# module_tester-v01.net
KiCad netlist of a schematic drawn in EAGLE
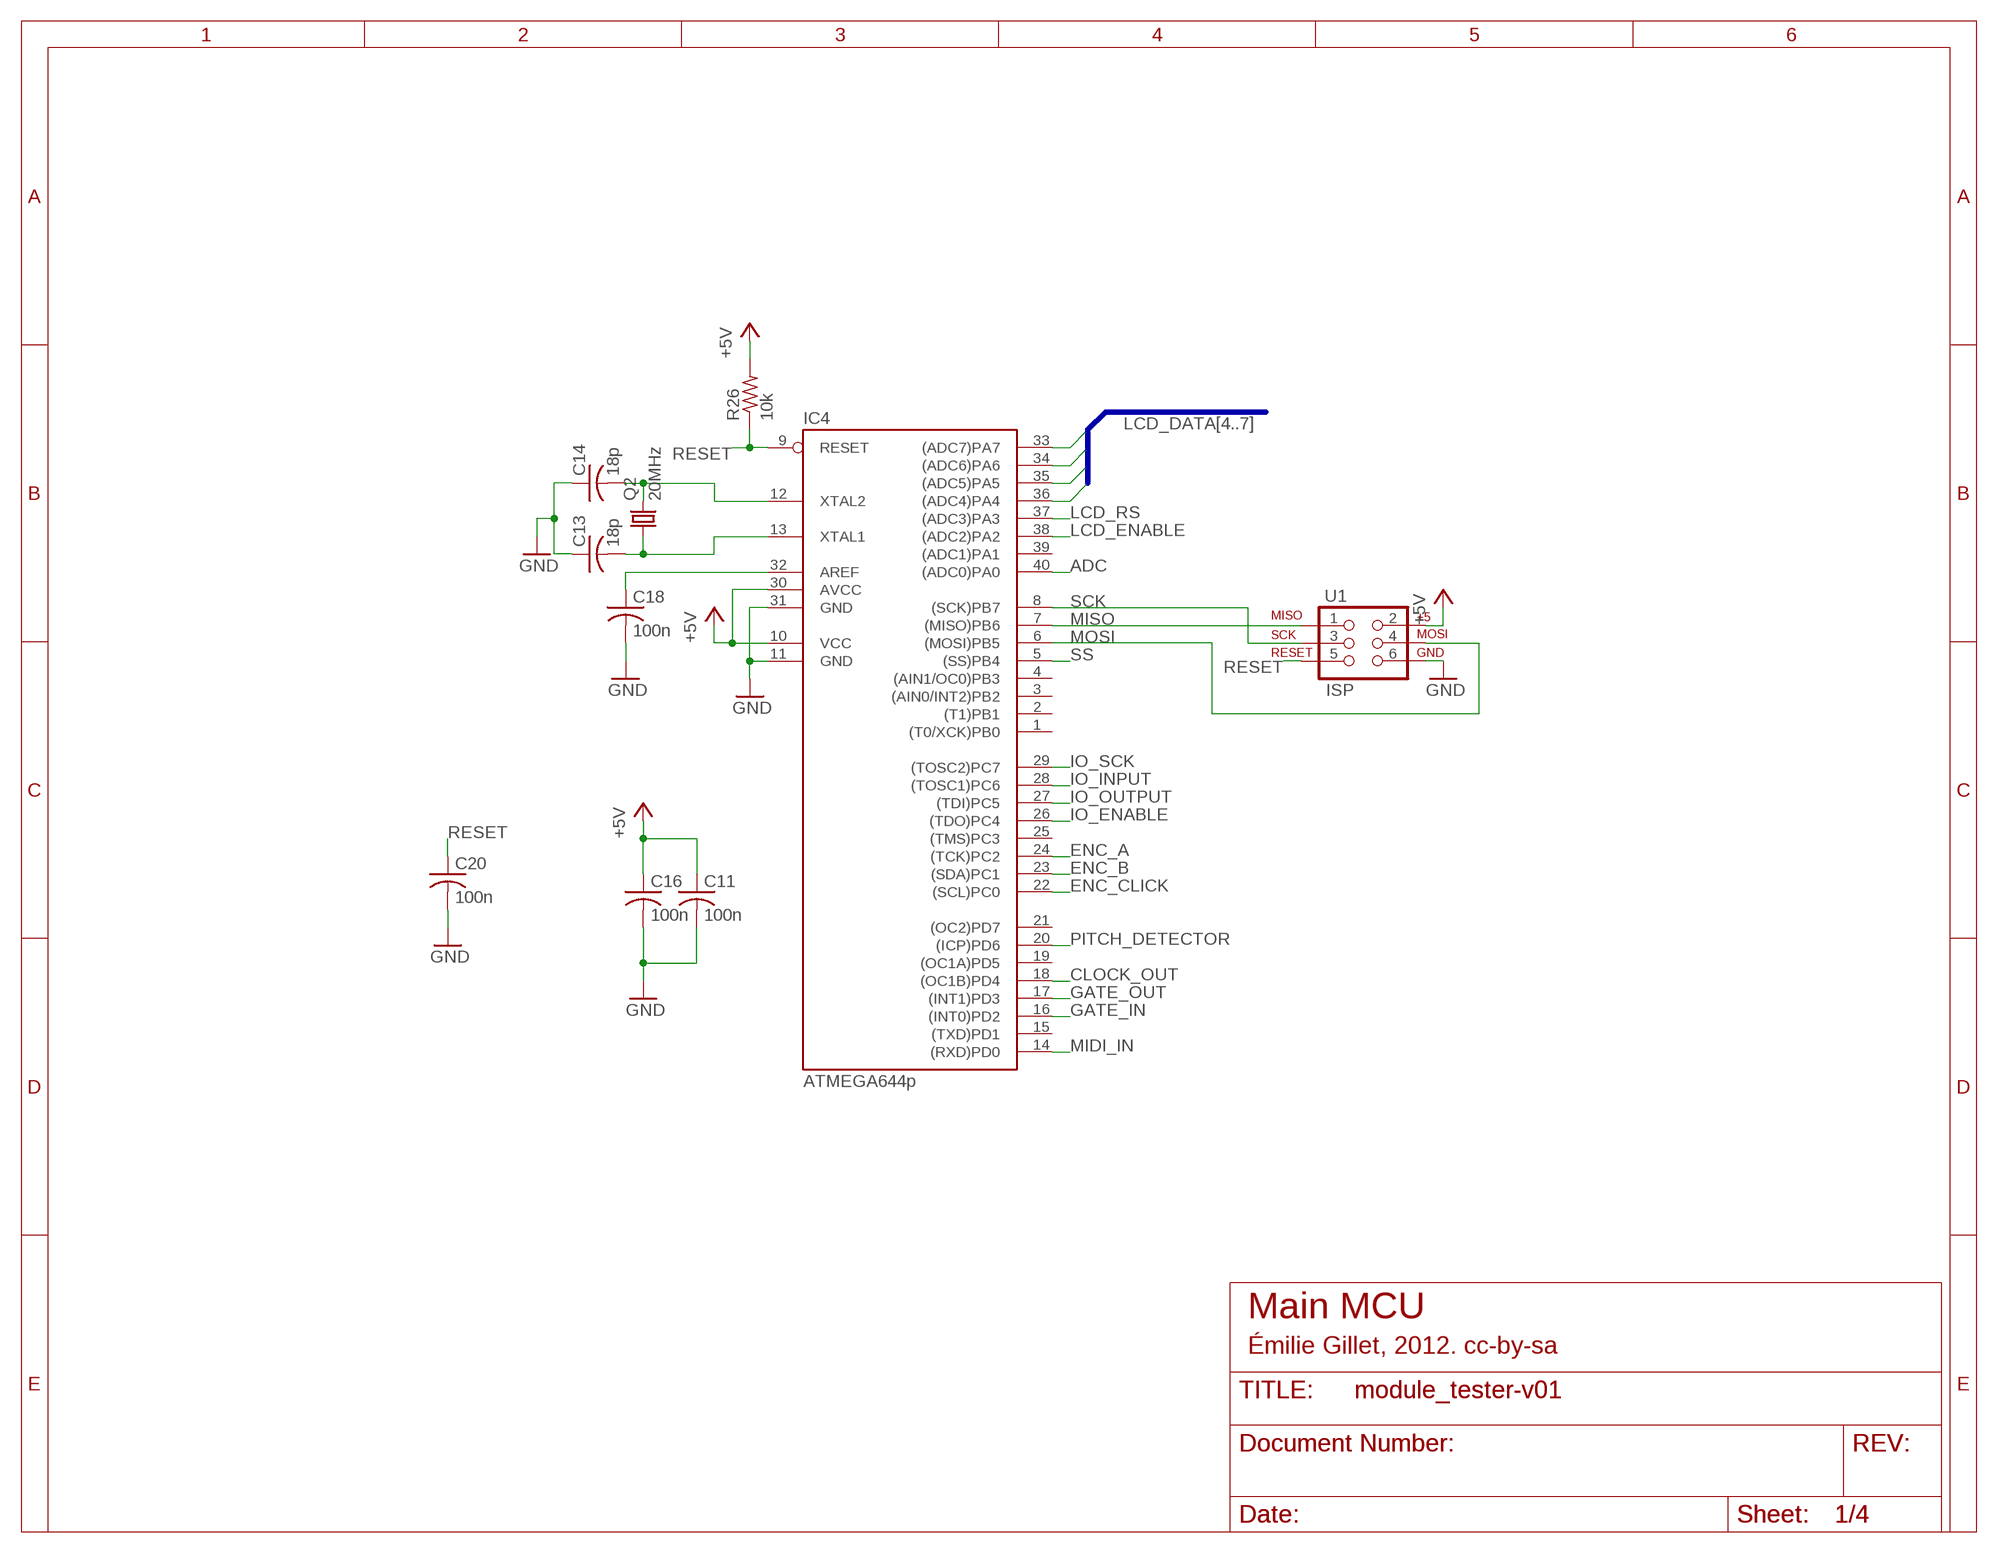
[diagram p0: schematic, sheet 1]
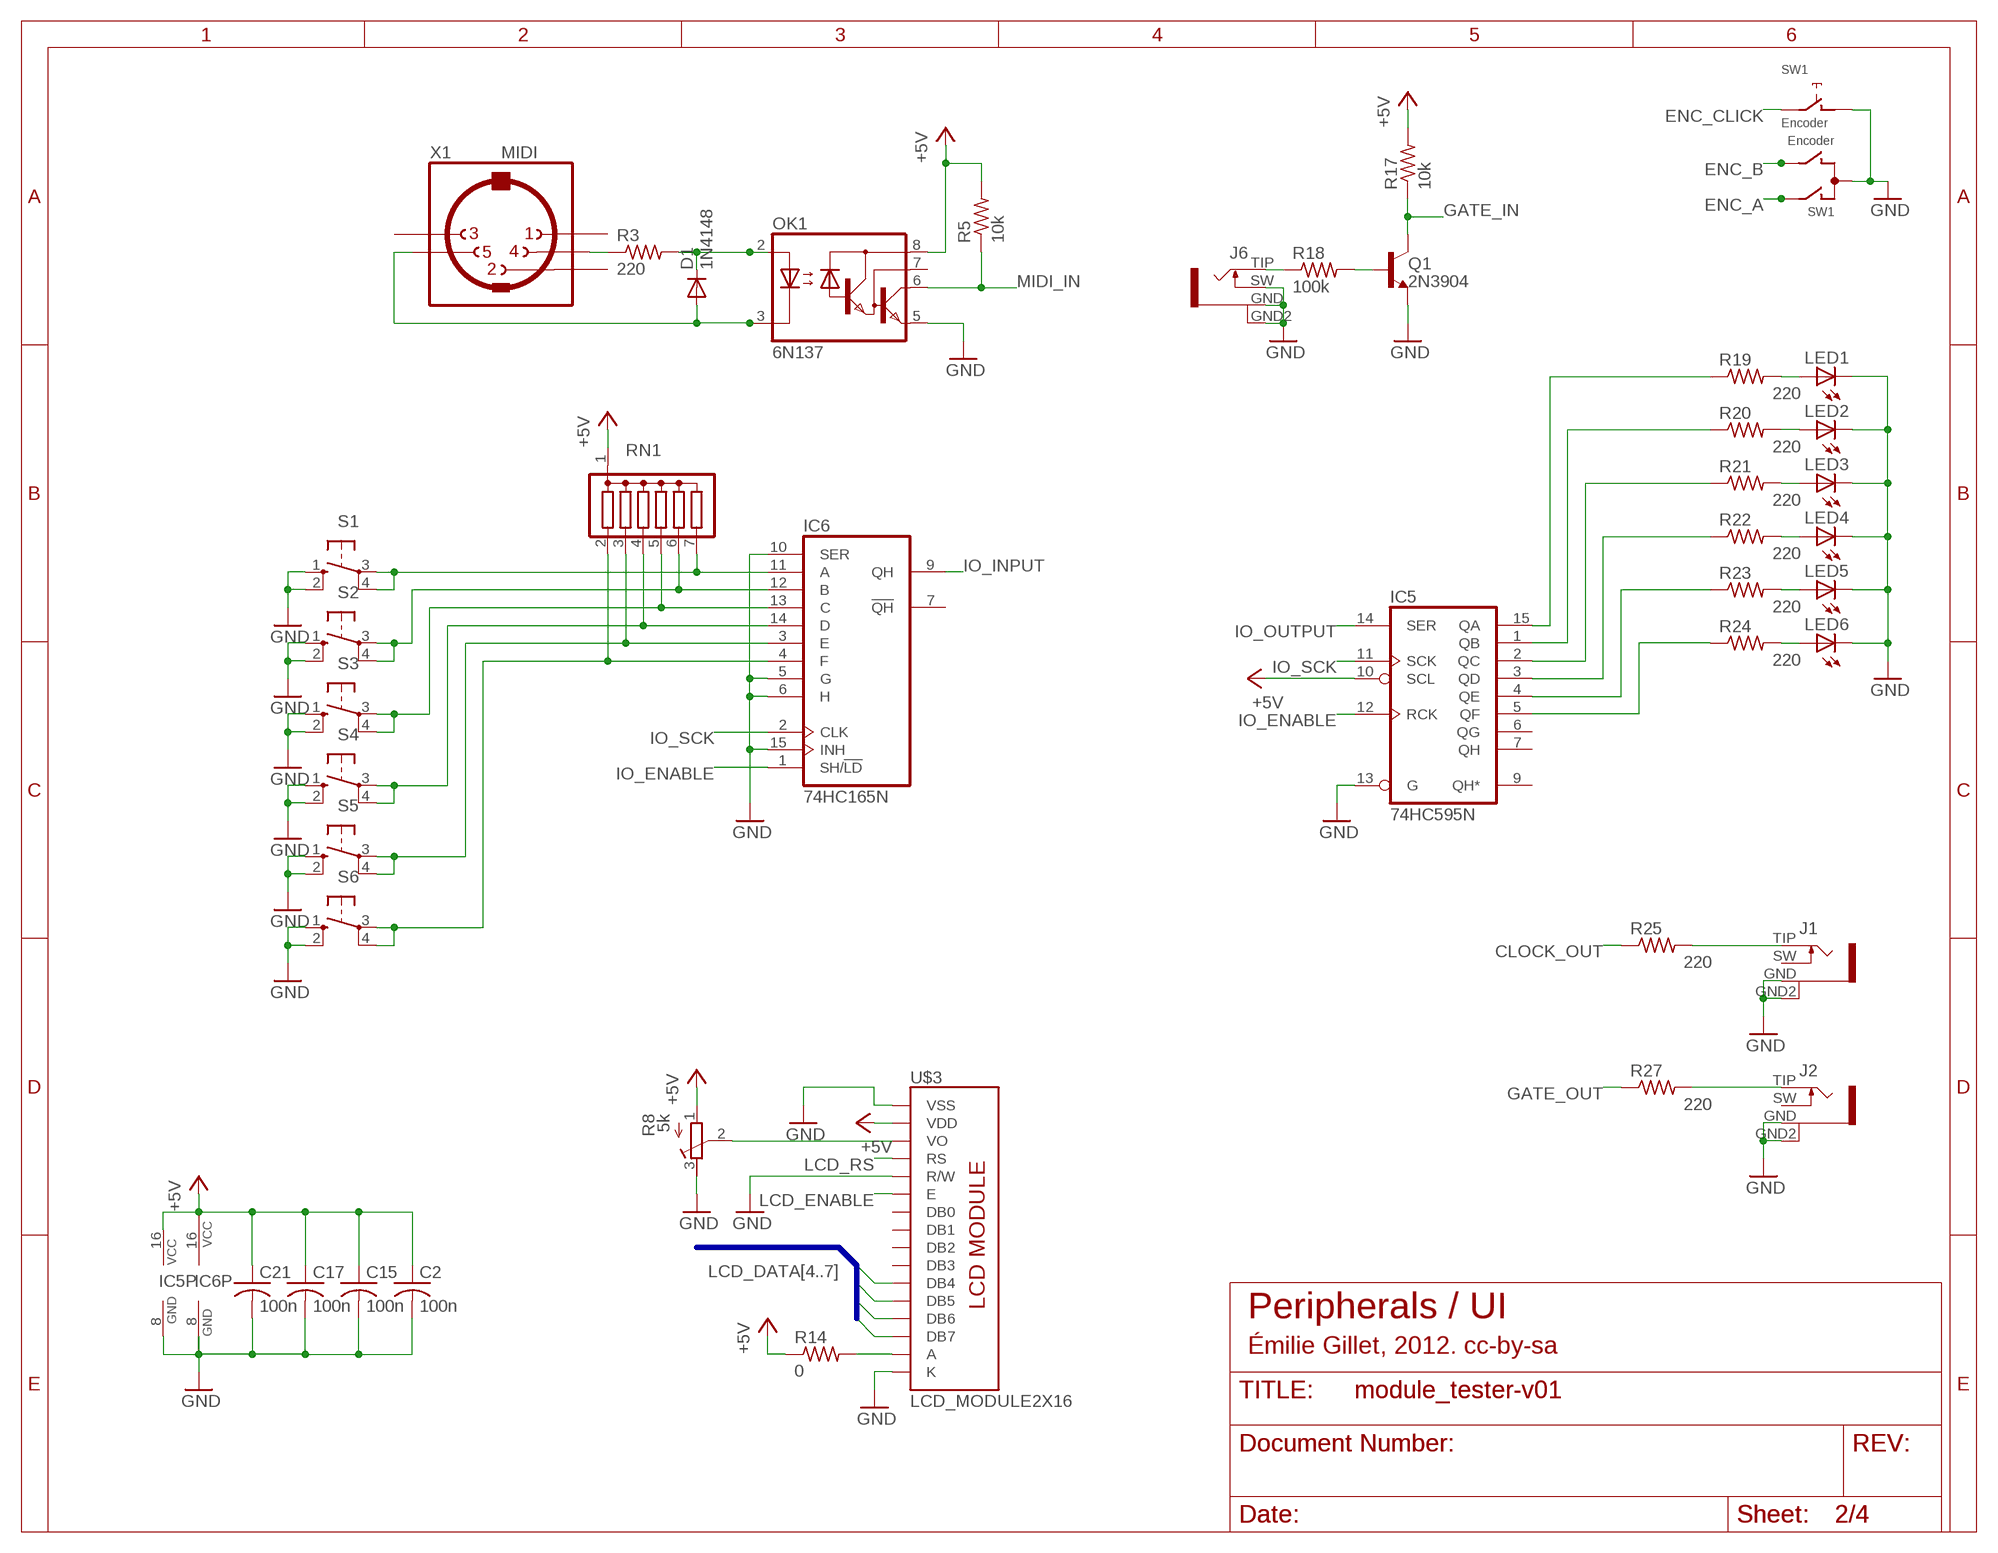
[diagram p1: schematic, sheet 2]
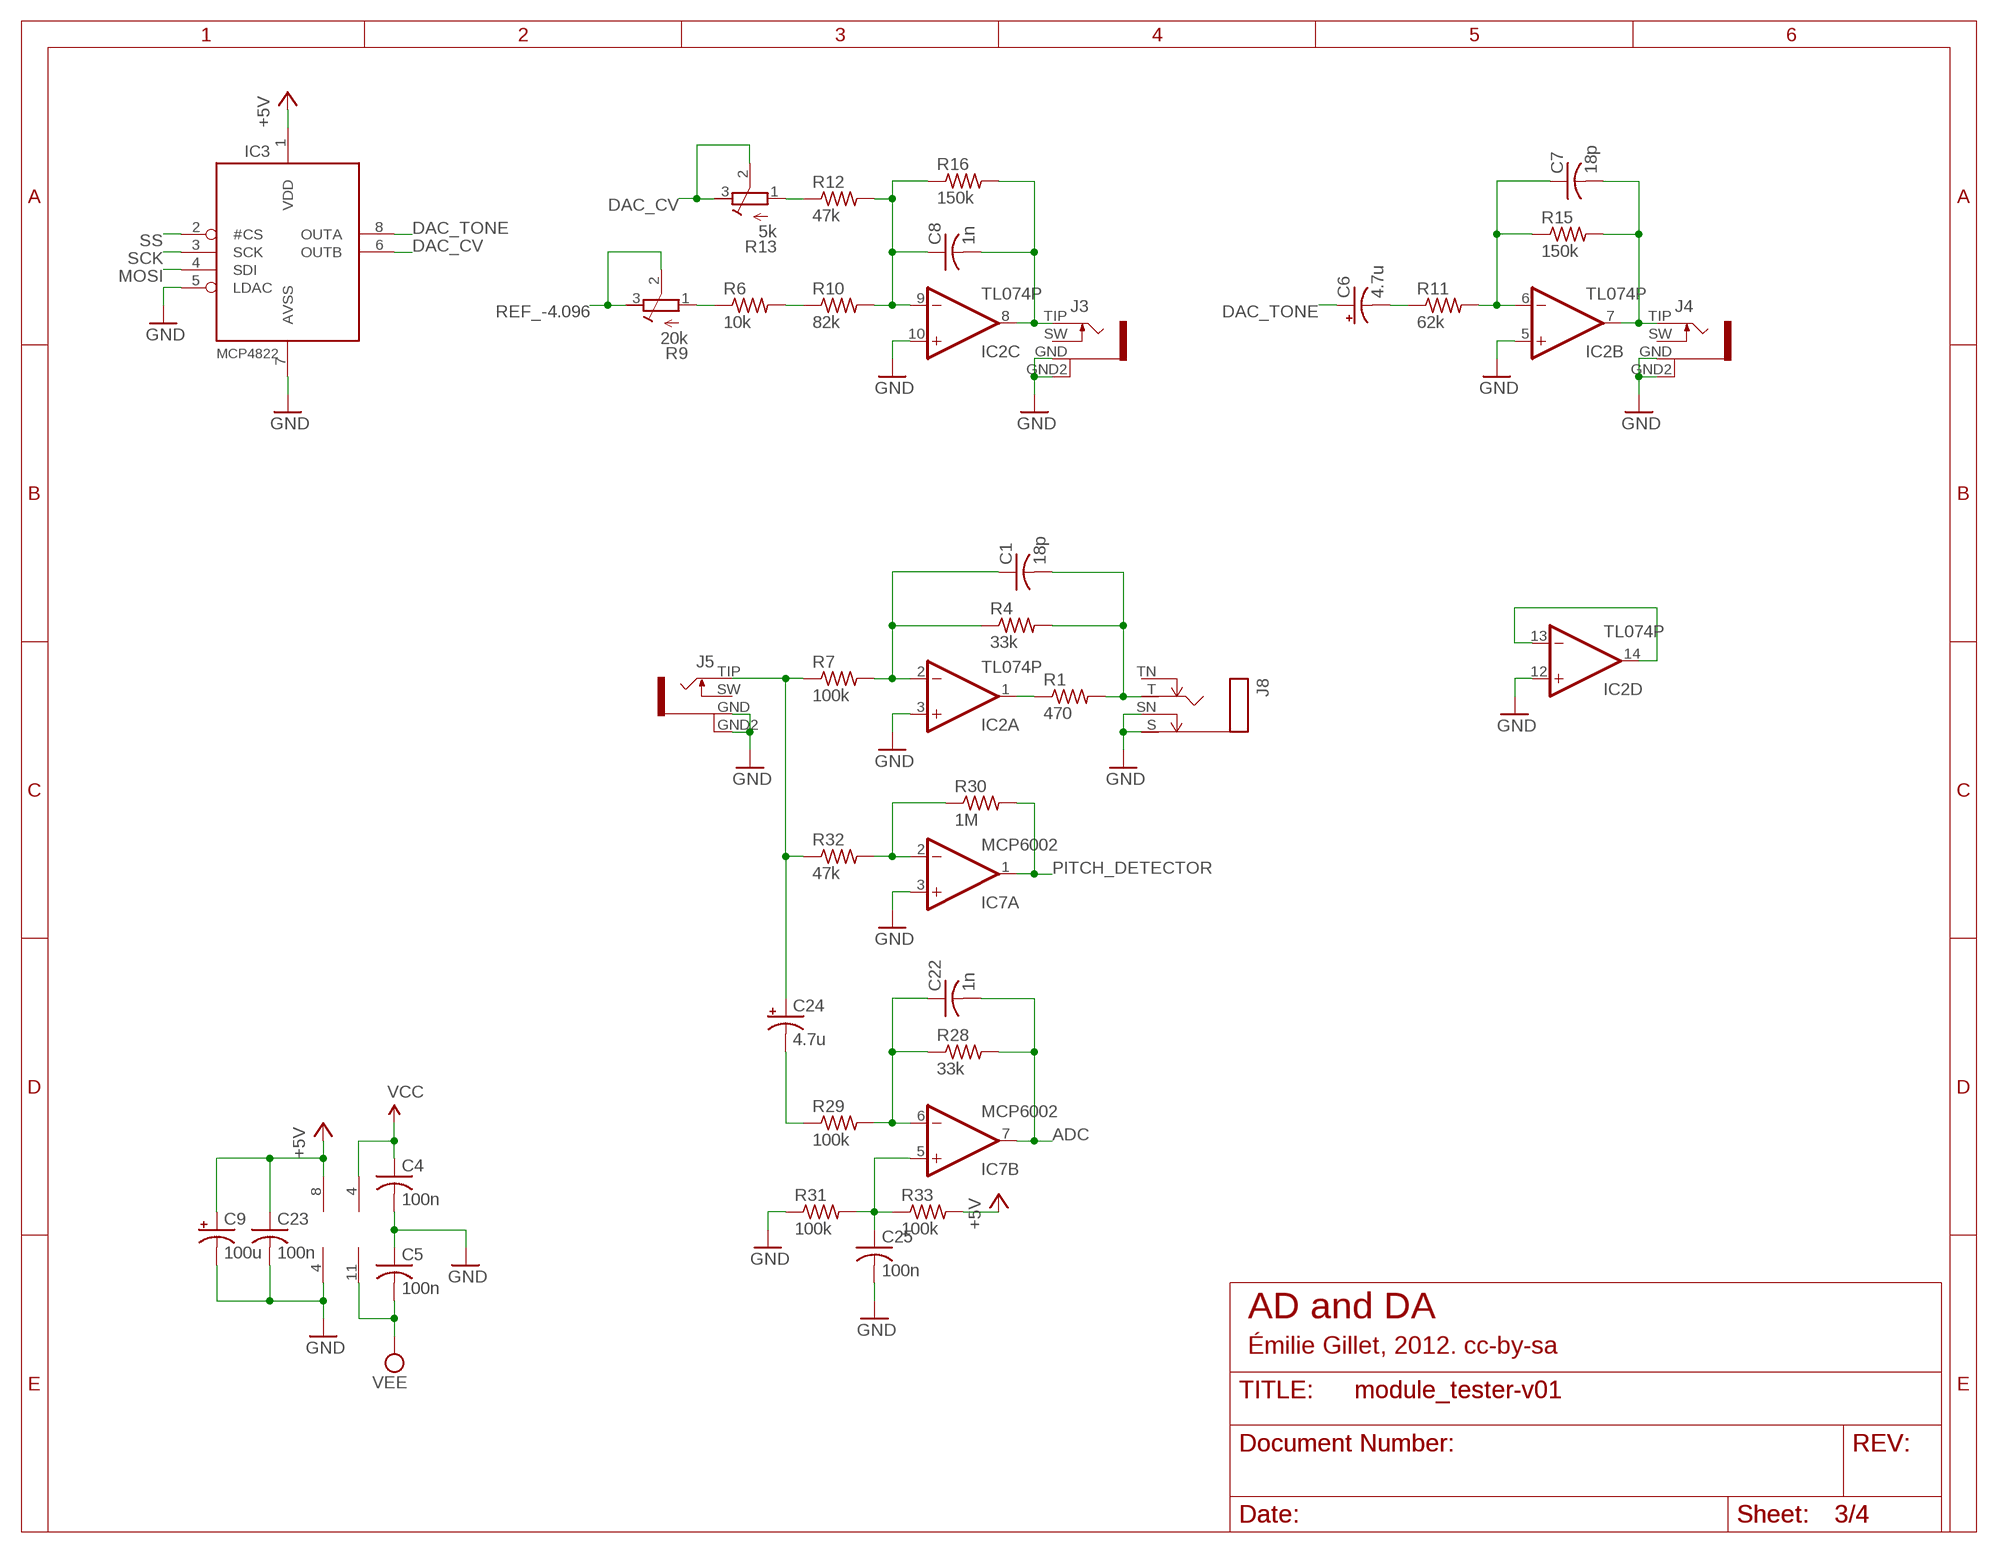
[diagram p2: schematic, sheet 3]
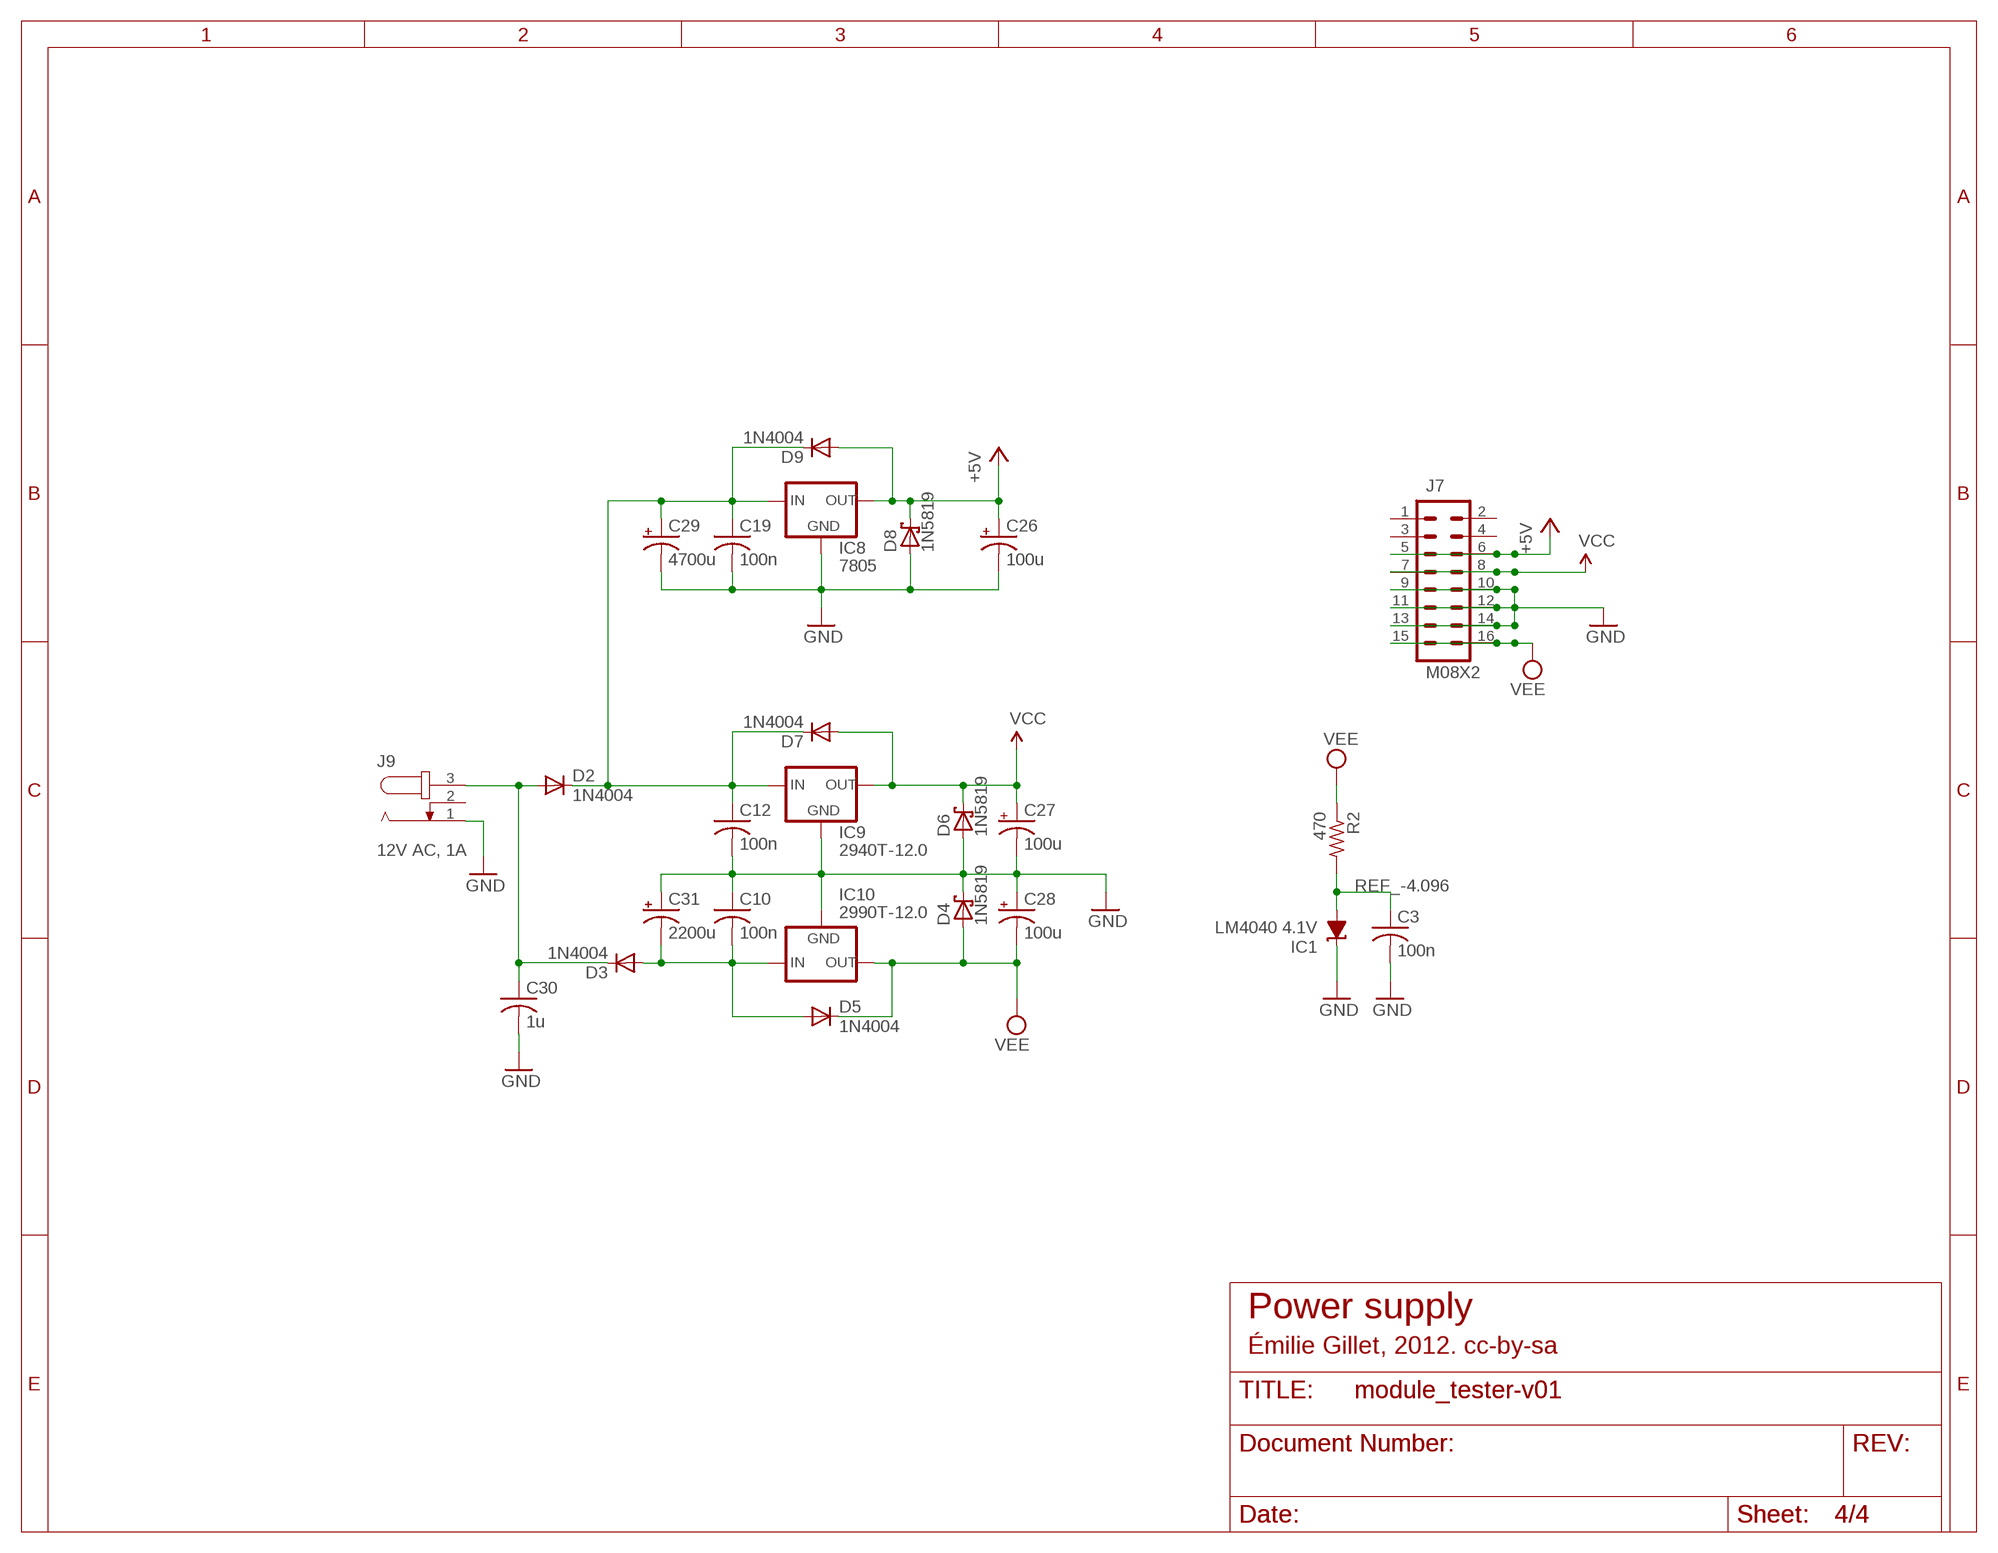
[diagram p3: schematic, sheet 4]

(export (version "E")
  (design (tool "Eeschema 10.0.6"))
  (components
    (comp (ref "C11")
      (value "100n")
      (footprint "eagle-import:C025-025X050")
      (libsource (lib "eagle-import") (part "C-US025-025X050"))
    )
    (comp (ref "C13")
      (value "18p")
      (footprint "eagle-import:C025-025X050")
      (libsource (lib "eagle-import") (part "C-US025-025X050"))
    )
    (comp (ref "C14")
      (value "18p")
      (footprint "eagle-import:C025-025X050")
      (libsource (lib "eagle-import") (part "C-US025-025X050"))
    )
    (comp (ref "C16")
      (value "100n")
      (footprint "eagle-import:C025-025X050")
      (libsource (lib "eagle-import") (part "C-US025-025X050"))
    )
    (comp (ref "C18")
      (value "100n")
      (footprint "eagle-import:C025-025X050")
      (libsource (lib "eagle-import") (part "C-US025-025X050"))
    )
    (comp (ref "C20")
      (value "100n")
      (footprint "eagle-import:C025-025X050")
      (libsource (lib "eagle-import") (part "C-US025-025X050"))
    )
    (comp (ref "IC4")
      (value "ATMEGA644p")
      (footprint "eagle-import:DIL40")
      (libsource (lib "eagle-import") (part "MEGA16-P"))
    )
    (comp (ref "Q2")
      (value "20MHz")
      (footprint "eagle-import:HC49U-V")
      (libsource (lib "eagle-import") (part "CRYSTALHC49U-V"))
    )
    (comp (ref "R26")
      (value "10k")
      (footprint "eagle-import:0204_7")
      (libsource (lib "eagle-import") (part "R-US_0204/7"))
    )
    (comp (ref "U1")
      (value "ISP")
      (footprint "eagle-import:2X3")
      (libsource (lib "eagle-import") (part "AVR_SPI_PRG_6PTH"))
    )
    (comp (ref "C3")
      (value "100n")
      (footprint "eagle-import:C025-025X050")
      (libsource (lib "eagle-import") (part "C-US025-025X050"))
    )
    (comp (ref "C10")
      (value "100n")
      (footprint "eagle-import:C025-025X050")
      (libsource (lib "eagle-import") (part "C-US025-025X050"))
    )
    (comp (ref "C12")
      (value "100n")
      (footprint "eagle-import:C025-025X050")
      (libsource (lib "eagle-import") (part "C-US025-025X050"))
    )
    (comp (ref "C19")
      (value "100n")
      (footprint "eagle-import:C025-025X050")
      (libsource (lib "eagle-import") (part "C-US025-025X050"))
    )
    (comp (ref "C26")
      (value "100u")
      (footprint "eagle-import:E2,5-7")
      (libsource (lib "eagle-import") (part "CPOL-USE2.5-7"))
    )
    (comp (ref "C27")
      (value "100u")
      (footprint "eagle-import:E2,5-7")
      (libsource (lib "eagle-import") (part "CPOL-USE2.5-7"))
    )
    (comp (ref "C28")
      (value "100u")
      (footprint "eagle-import:E2,5-7")
      (libsource (lib "eagle-import") (part "CPOL-USE2.5-7"))
    )
    (comp (ref "C29")
      (value "4700u")
      (footprint "eagle-import:E7,5-16")
      (libsource (lib "eagle-import") (part "CPOL-USE7.5-16"))
    )
    (comp (ref "C30")
      (value "1u")
      (footprint "eagle-import:C075-052X106")
      (libsource (lib "eagle-import") (part "C-US075-052X106"))
    )
    (comp (ref "C31")
      (value "2200u")
      (footprint "eagle-import:E5-13")
      (libsource (lib "eagle-import") (part "CPOL-USE5-13"))
    )
    (comp (ref "D2")
      (value "1N4004")
      (footprint "eagle-import:DO41-10")
      (libsource (lib "eagle-import") (part "1N4004"))
    )
    (comp (ref "D3")
      (value "1N4004")
      (footprint "eagle-import:DO41-10")
      (libsource (lib "eagle-import") (part "1N4004"))
    )
    (comp (ref "D4")
      (value "1N5819")
      (footprint "eagle-import:DO41-7.6")
      (libsource (lib "eagle-import") (part "1N5819-T"))
    )
    (comp (ref "D5")
      (value "1N4004")
      (footprint "eagle-import:DO41-10")
      (libsource (lib "eagle-import") (part "1N4004"))
    )
    (comp (ref "D6")
      (value "1N5819")
      (footprint "eagle-import:DO41-7.6")
      (libsource (lib "eagle-import") (part "1N5819-T"))
    )
    (comp (ref "D7")
      (value "1N4004")
      (footprint "eagle-import:DO41-10")
      (libsource (lib "eagle-import") (part "1N4004"))
    )
    (comp (ref "D8")
      (value "1N5819")
      (footprint "eagle-import:DO41-7.6")
      (libsource (lib "eagle-import") (part "1N5819-T"))
    )
    (comp (ref "D9")
      (value "1N4004")
      (footprint "eagle-import:DO41-10")
      (libsource (lib "eagle-import") (part "1N4004"))
    )
    (comp (ref "IC1")
      (value "LM4040 4.1V")
      (footprint "eagle-import:LP_O-PBCY-W3")
      (libsource (lib "eagle-import") (part "LM4041LPC12"))
    )
    (comp (ref "IC8")
      (value "7805")
      (footprint "eagle-import:78XXS")
      (libsource (lib "eagle-import") (part "78XXS"))
    )
    (comp (ref "IC9")
      (value "2940T-12.0")
      (footprint "eagle-import:78XXL")
      (libsource (lib "eagle-import") (part "78XXL"))
    )
    (comp (ref "IC10")
      (value "2990T-12.0")
      (footprint "eagle-import:79XXS")
      (libsource (lib "eagle-import") (part "79XXS"))
    )
    (comp (ref "J7")
      (value "M08X2")
      (footprint "eagle-import:2X8")
      (libsource (lib "eagle-import") (part "M08X2"))
    )
    (comp (ref "J9")
      (value "JACK-PLUG2")
      (footprint "eagle-import:SPC4078_BIG_HOLES")
      (libsource (lib "eagle-import") (part "JACK-PLUG2"))
    )
    (comp (ref "R2")
      (value "470")
      (footprint "eagle-import:0204_7")
      (libsource (lib "eagle-import") (part "resistor_R-US_0204/7"))
    )
    (comp (ref "C2")
      (value "100n")
      (footprint "eagle-import:C025-025X050")
      (libsource (lib "eagle-import") (part "C-US025-025X050"))
    )
    (comp (ref "C15")
      (value "100n")
      (footprint "eagle-import:C025-025X050")
      (libsource (lib "eagle-import") (part "C-US025-025X050"))
    )
    (comp (ref "C17")
      (value "100n")
      (footprint "eagle-import:C025-025X050")
      (libsource (lib "eagle-import") (part "C-US025-025X050"))
    )
    (comp (ref "C21")
      (value "100n")
      (footprint "eagle-import:C025-025X050")
      (libsource (lib "eagle-import") (part "C-US025-025X050"))
    )
    (comp (ref "D1")
      (value "1N4148")
      (footprint "eagle-import:D-5")
      (libsource (lib "eagle-import") (part "DIODE-D-5"))
    )
    (comp (ref "IC5")
      (value "74HC595N")
      (footprint "eagle-import:DIL16")
      (libsource (lib "eagle-import") (part "74595NHC"))
    )
    (comp (ref "IC6")
      (value "74HC165N")
      (footprint "eagle-import:DIL16")
      (libsource (lib "eagle-import") (part "74165NLS"))
    )
    (comp (ref "J1")
      (value "PJ301WQP")
      (footprint "eagle-import:WQP_PJ_301BM")
      (libsource (lib "eagle-import") (part "PJ301WQP"))
    )
    (comp (ref "J2")
      (value "PJ301WQP")
      (footprint "eagle-import:WQP_PJ_301BM")
      (libsource (lib "eagle-import") (part "PJ301WQP"))
    )
    (comp (ref "J6")
      (value "PJ301WQP")
      (footprint "eagle-import:WQP_PJ_301BM")
      (libsource (lib "eagle-import") (part "PJ301WQP"))
    )
    (comp (ref "LED1")
      (value "LED3MM")
      (footprint "eagle-import:LED3MM")
      (libsource (lib "eagle-import") (part "LED3MM"))
    )
    (comp (ref "LED2")
      (value "LED3MM")
      (footprint "eagle-import:LED3MM")
      (libsource (lib "eagle-import") (part "LED3MM"))
    )
    (comp (ref "LED3")
      (value "LED3MM")
      (footprint "eagle-import:LED3MM")
      (libsource (lib "eagle-import") (part "LED3MM"))
    )
    (comp (ref "LED4")
      (value "LED3MM")
      (footprint "eagle-import:LED3MM")
      (libsource (lib "eagle-import") (part "LED3MM"))
    )
    (comp (ref "LED5")
      (value "LED3MM")
      (footprint "eagle-import:LED3MM")
      (libsource (lib "eagle-import") (part "LED3MM"))
    )
    (comp (ref "LED6")
      (value "LED3MM")
      (footprint "eagle-import:LED3MM")
      (libsource (lib "eagle-import") (part "LED3MM"))
    )
    (comp (ref "OK1")
      (value "6N137")
      (footprint "eagle-import:DIL08")
      (libsource (lib "eagle-import") (part "6N138"))
    )
    (comp (ref "Q1")
      (value "2N3904")
      (footprint "eagle-import:TO92-")
      (libsource (lib "eagle-import") (part "2N3904"))
    )
    (comp (ref "R3")
      (value "220")
      (footprint "eagle-import:0204_7")
      (libsource (lib "eagle-import") (part "R-US_0204/7"))
    )
    (comp (ref "R5")
      (value "10k")
      (footprint "eagle-import:0204_7")
      (libsource (lib "eagle-import") (part "R-US_0204/7"))
    )
    (comp (ref "R8")
      (value "5k")
      (footprint "eagle-import:RTRIM3339P")
      (libsource (lib "eagle-import") (part "R-TRIMM3339P"))
    )
    (comp (ref "R14")
      (value "0")
      (footprint "eagle-import:0204_7")
      (libsource (lib "eagle-import") (part "R-US_0204/7"))
    )
    (comp (ref "R17")
      (value "10k")
      (footprint "eagle-import:0204_7")
      (libsource (lib "eagle-import") (part "R-US_0204/7"))
    )
    (comp (ref "R18")
      (value "100k")
      (footprint "eagle-import:0204_7")
      (libsource (lib "eagle-import") (part "R-US_0204/7"))
    )
    (comp (ref "R19")
      (value "220")
      (footprint "eagle-import:0204_7")
      (libsource (lib "eagle-import") (part "R-US_0204/7"))
    )
    (comp (ref "R20")
      (value "220")
      (footprint "eagle-import:0204_7")
      (libsource (lib "eagle-import") (part "R-US_0204/7"))
    )
    (comp (ref "R21")
      (value "220")
      (footprint "eagle-import:0204_7")
      (libsource (lib "eagle-import") (part "R-US_0204/7"))
    )
    (comp (ref "R22")
      (value "220")
      (footprint "eagle-import:0204_7")
      (libsource (lib "eagle-import") (part "R-US_0204/7"))
    )
    (comp (ref "R23")
      (value "220")
      (footprint "eagle-import:0204_7")
      (libsource (lib "eagle-import") (part "R-US_0204/7"))
    )
    (comp (ref "R24")
      (value "220")
      (footprint "eagle-import:0204_7")
      (libsource (lib "eagle-import") (part "R-US_0204/7"))
    )
    (comp (ref "R25")
      (value "220")
      (footprint "eagle-import:0204_7")
      (libsource (lib "eagle-import") (part "R-US_0204/7"))
    )
    (comp (ref "R27")
      (value "220")
      (footprint "eagle-import:0204_7")
      (libsource (lib "eagle-import") (part "R-US_0204/7"))
    )
    (comp (ref "RN1")
      (value "G06R")
      (footprint "eagle-import:SIL7")
      (libsource (lib "eagle-import") (part "G06R"))
    )
    (comp (ref "S1")
      (value "40-XX")
      (footprint "eagle-import:B3F-40XX")
      (libsource (lib "eagle-import") (part "40-XX"))
    )
    (comp (ref "S2")
      (value "40-XX")
      (footprint "eagle-import:B3F-40XX")
      (libsource (lib "eagle-import") (part "40-XX"))
    )
    (comp (ref "S3")
      (value "40-XX")
      (footprint "eagle-import:B3F-40XX")
      (libsource (lib "eagle-import") (part "40-XX"))
    )
    (comp (ref "S4")
      (value "40-XX")
      (footprint "eagle-import:B3F-40XX")
      (libsource (lib "eagle-import") (part "40-XX"))
    )
    (comp (ref "S5")
      (value "40-XX")
      (footprint "eagle-import:B3F-40XX")
      (libsource (lib "eagle-import") (part "40-XX"))
    )
    (comp (ref "S6")
      (value "40-XX")
      (footprint "eagle-import:B3F-40XX")
      (libsource (lib "eagle-import") (part "40-XX"))
    )
    (comp (ref "SW1")
      (value "Encoder")
      (footprint "eagle-import:ALPS_EC12E_SW")
      (libsource (lib "eagle-import") (part "EC12E_SW"))
    )
    (comp (ref "U$3")
      (value "LCD_MODULE2X16")
      (footprint "eagle-import:LCD_MODULE_2X16")
      (libsource (lib "eagle-import") (part "LCD_MODULE2X16"))
    )
    (comp (ref "X1")
      (value "MIDI")
      (footprint "eagle-import:MAB5SH")
      (libsource (lib "eagle-import") (part "MAB5SH"))
    )
    (comp (ref "C1")
      (value "18p")
      (footprint "eagle-import:C025-025X050")
      (libsource (lib "eagle-import") (part "C-US025-025X050"))
    )
    (comp (ref "C4")
      (value "100n")
      (footprint "eagle-import:C025-025X050")
      (libsource (lib "eagle-import") (part "C-US025-025X050"))
    )
    (comp (ref "C5")
      (value "100n")
      (footprint "eagle-import:C025-025X050")
      (libsource (lib "eagle-import") (part "C-US025-025X050"))
    )
    (comp (ref "C6")
      (value "4.7u")
      (footprint "eagle-import:E2,5-6")
      (libsource (lib "eagle-import") (part "CPOL-USE2.5-6"))
    )
    (comp (ref "C7")
      (value "18p")
      (footprint "eagle-import:C025-025X050")
      (libsource (lib "eagle-import") (part "C-US025-025X050"))
    )
    (comp (ref "C8")
      (value "1n")
      (footprint "eagle-import:C025-025X050")
      (libsource (lib "eagle-import") (part "C-US025-025X050"))
    )
    (comp (ref "C9")
      (value "100u")
      (footprint "eagle-import:E2,5-7")
      (libsource (lib "eagle-import") (part "CPOL-USE2.5-7"))
    )
    (comp (ref "C22")
      (value "1n")
      (footprint "eagle-import:C025-025X050")
      (libsource (lib "eagle-import") (part "C-US025-025X050"))
    )
    (comp (ref "C23")
      (value "100n")
      (footprint "eagle-import:C025-025X050")
      (libsource (lib "eagle-import") (part "C-US025-025X050"))
    )
    (comp (ref "C24")
      (value "4.7u")
      (footprint "eagle-import:E2,5-6")
      (libsource (lib "eagle-import") (part "CPOL-USE2.5-6"))
    )
    (comp (ref "C25")
      (value "100n")
      (footprint "eagle-import:C025-025X050")
      (libsource (lib "eagle-import") (part "C-US025-025X050"))
    )
    (comp (ref "IC2")
      (value "TL074P")
      (footprint "eagle-import:DIL14")
      (libsource (lib "eagle-import") (part "TL074P"))
    )
    (comp (ref "IC3")
      (value "MCP4822")
      (footprint "eagle-import:DIL08")
      (libsource (lib "eagle-import") (part "MCP4822"))
    )
    (comp (ref "IC7")
      (value "MCP6002")
      (footprint "eagle-import:DIL08")
      (libsource (lib "eagle-import") (part "TL072P"))
    )
    (comp (ref "J3")
      (value "PJ301WQP")
      (footprint "eagle-import:WQP_PJ_301BM")
      (libsource (lib "eagle-import") (part "PJ301WQP"))
    )
    (comp (ref "J4")
      (value "PJ301WQP")
      (footprint "eagle-import:WQP_PJ_301BM")
      (libsource (lib "eagle-import") (part "PJ301WQP"))
    )
    (comp (ref "J5")
      (value "PJ301WQP")
      (footprint "eagle-import:WQP_PJ_301BM")
      (libsource (lib "eagle-import") (part "PJ301WQP"))
    )
    (comp (ref "J8")
      (value "MONOSWSLIM")
      (footprint "eagle-import:NRJ4HF")
      (libsource (lib "eagle-import") (part "MONOSWSLIM"))
    )
    (comp (ref "R1")
      (value "470")
      (footprint "eagle-import:0204_7")
      (libsource (lib "eagle-import") (part "R-US_0204/7"))
    )
    (comp (ref "R4")
      (value "33k")
      (footprint "eagle-import:0204_7")
      (libsource (lib "eagle-import") (part "R-US_0204/7"))
    )
    (comp (ref "R6")
      (value "10k")
      (footprint "eagle-import:0204_7")
      (libsource (lib "eagle-import") (part "R-US_0204/7"))
    )
    (comp (ref "R7")
      (value "100k")
      (footprint "eagle-import:0204_7")
      (libsource (lib "eagle-import") (part "R-US_0204/7"))
    )
    (comp (ref "R9")
      (value "20k")
      (footprint "eagle-import:RTRIM3296W")
      (libsource (lib "eagle-import") (part "R-TRIMM3296W"))
    )
    (comp (ref "R10")
      (value "82k")
      (footprint "eagle-import:0204_7")
      (libsource (lib "eagle-import") (part "R-US_0204/7"))
    )
    (comp (ref "R11")
      (value "62k")
      (footprint "eagle-import:0204_7")
      (libsource (lib "eagle-import") (part "R-US_0204/7"))
    )
    (comp (ref "R12")
      (value "47k")
      (footprint "eagle-import:0204_7")
      (libsource (lib "eagle-import") (part "R-US_0204/7"))
    )
    (comp (ref "R13")
      (value "5k")
      (footprint "eagle-import:RTRIM3296W")
      (libsource (lib "eagle-import") (part "R-TRIMM3296W"))
    )
    (comp (ref "R15")
      (value "150k")
      (footprint "eagle-import:0204_7")
      (libsource (lib "eagle-import") (part "R-US_0204/7"))
    )
    (comp (ref "R16")
      (value "150k")
      (footprint "eagle-import:0204_7")
      (libsource (lib "eagle-import") (part "R-US_0204/7"))
    )
    (comp (ref "R28")
      (value "33k")
      (footprint "eagle-import:0204_7")
      (libsource (lib "eagle-import") (part "R-US_0204/7"))
    )
    (comp (ref "R29")
      (value "100k")
      (footprint "eagle-import:0204_7")
      (libsource (lib "eagle-import") (part "R-US_0204/7"))
    )
    (comp (ref "R30")
      (value "1M")
      (footprint "eagle-import:0204_7")
      (libsource (lib "eagle-import") (part "R-US_0204/7"))
    )
    (comp (ref "R31")
      (value "100k")
      (footprint "eagle-import:0204_7")
      (libsource (lib "eagle-import") (part "R-US_0204/7"))
    )
    (comp (ref "R32")
      (value "47k")
      (footprint "eagle-import:0204_7")
      (libsource (lib "eagle-import") (part "R-US_0204/7"))
    )
    (comp (ref "R33")
      (value "100k")
      (footprint "eagle-import:0204_7")
      (libsource (lib "eagle-import") (part "R-US_0204/7"))
    )
  )
  (nets
    (net (code "1") (name "+5V") (class "Default")
      (node (ref "C11") (pin "1") (pinfunction "1_1") (pintype "passive"))
      (node (ref "C15") (pin "1") (pinfunction "1_1") (pintype "passive"))
      (node (ref "C16") (pin "1") (pinfunction "1_1") (pintype "passive"))
      (node (ref "C17") (pin "1") (pinfunction "1_1") (pintype "passive"))
      (node (ref "C2") (pin "1") (pinfunction "1_1") (pintype "passive"))
      (node (ref "C21") (pin "1") (pinfunction "1_1") (pintype "passive"))
      (node (ref "C23") (pin "1") (pinfunction "1_1") (pintype "passive"))
      (node (ref "C26") (pin "+") (pinfunction "+_+") (pintype "passive"))
      (node (ref "C9") (pin "+") (pinfunction "+_+") (pintype "passive"))
      (node (ref "D8") (pin "C") (pinfunction "C_C") (pintype "passive"))
      (node (ref "D9") (pin "A") (pinfunction "A_A") (pintype "passive"))
      (node (ref "IC3") (pin "1") (pinfunction "VDD_1") (pintype "power_in"))
      (node (ref "IC4") (pin "10") (pinfunction "VCC_10") (pintype "power_in"))
      (node (ref "IC4") (pin "30") (pinfunction "AVCC_30") (pintype "power_in"))
      (node (ref "IC5") (pin "10") (pinfunction "SCL_10") (pintype "input"))
      (node (ref "IC5") (pin "16") (pinfunction "VCC_16") (pintype "power_in"))
      (node (ref "IC6") (pin "16") (pinfunction "VCC_16") (pintype "power_in"))
      (node (ref "IC7") (pin "8") (pinfunction "V+_8") (pintype "power_in"))
      (node (ref "IC8") (pin "OUT") (pinfunction "OUT_OUT") (pintype "passive"))
      (node (ref "J7") (pin "5") (pinfunction "5_5") (pintype "passive"))
      (node (ref "J7") (pin "6") (pinfunction "6_6") (pintype "passive"))
      (node (ref "OK1") (pin "8") (pinfunction "VCC_8") (pintype "passive"))
      (node (ref "R14") (pin "1") (pinfunction "1_1") (pintype "passive"))
      (node (ref "R17") (pin "2") (pinfunction "2_2") (pintype "passive"))
      (node (ref "R26") (pin "2") (pinfunction "2_2") (pintype "passive"))
      (node (ref "R33") (pin "2") (pinfunction "2_2") (pintype "passive"))
      (node (ref "R5") (pin "2") (pinfunction "2_2") (pintype "passive"))
      (node (ref "R8") (pin "1") (pinfunction "E_1") (pintype "passive"))
      (node (ref "RN1") (pin "1") (pinfunction "1_1") (pintype "passive"))
      (node (ref "U$3") (pin "2") (pinfunction "VDD_2") (pintype "power_in"))
      (node (ref "U1") (pin "2") (pinfunction "2_2") (pintype "passive"))
    )
    (net (code "4") (name "ADC") (class "Default")
      (node (ref "C22") (pin "2") (pinfunction "2_2") (pintype "passive"))
      (node (ref "IC4") (pin "40") (pinfunction "(ADC0)PA0_40") (pintype "bidirectional"))
      (node (ref "IC7") (pin "7") (pinfunction "OUT_7") (pintype "output"))
      (node (ref "R28") (pin "2") (pinfunction "2_2") (pintype "passive"))
    )
    (net (code "5") (name "CLOCK_OUT") (class "Default")
      (node (ref "IC4") (pin "18") (pinfunction "(OC1B)PD4_18") (pintype "bidirectional"))
      (node (ref "R25") (pin "1") (pinfunction "1_1") (pintype "passive"))
    )
    (net (code "6") (name "DAC_CV") (class "Default")
      (node (ref "IC3") (pin "6") (pinfunction "OUTB_6") (pintype "output"))
      (node (ref "R13") (pin "2") (pinfunction "S_2") (pintype "passive"))
      (node (ref "R13") (pin "3") (pinfunction "A_3") (pintype "passive"))
    )
    (net (code "7") (name "DAC_TONE") (class "Default")
      (node (ref "C6") (pin "+") (pinfunction "+_+") (pintype "passive"))
      (node (ref "IC3") (pin "8") (pinfunction "OUTA_8") (pintype "output"))
    )
    (net (code "8") (name "ENC_A") (class "Default")
      (node (ref "IC4") (pin "24") (pinfunction "(TCK)PC2_24") (pintype "bidirectional"))
      (node (ref "SW1") (pin "A") (pinfunction "A_A") (pintype "passive"))
    )
    (net (code "9") (name "ENC_B") (class "Default")
      (node (ref "IC4") (pin "23") (pinfunction "(SDA)PC1_23") (pintype "bidirectional"))
      (node (ref "SW1") (pin "B") (pinfunction "B_B") (pintype "passive"))
    )
    (net (code "10") (name "ENC_CLICK") (class "Default")
      (node (ref "IC4") (pin "22") (pinfunction "(SCL)PC0_22") (pintype "bidirectional"))
      (node (ref "SW1") (pin "E") (pinfunction "2_E") (pintype "passive"))
    )
    (net (code "11") (name "GATE_IN") (class "Default")
      (node (ref "IC4") (pin "16") (pinfunction "(INT0)PD2_16") (pintype "bidirectional"))
      (node (ref "Q1") (pin "1") (pinfunction "C_1") (pintype "passive"))
      (node (ref "R17") (pin "1") (pinfunction "1_1") (pintype "passive"))
    )
    (net (code "12") (name "GATE_OUT") (class "Default")
      (node (ref "IC4") (pin "17") (pinfunction "(INT1)PD3_17") (pintype "bidirectional"))
      (node (ref "R27") (pin "1") (pinfunction "1_1") (pintype "passive"))
    )
    (net (code "13") (name "GND") (class "Default")
      (node (ref "C10") (pin "1") (pinfunction "1_1") (pintype "passive"))
      (node (ref "C11") (pin "2") (pinfunction "2_2") (pintype "passive"))
      (node (ref "C12") (pin "2") (pinfunction "2_2") (pintype "passive"))
      (node (ref "C13") (pin "1") (pinfunction "1_1") (pintype "passive"))
      (node (ref "C14") (pin "1") (pinfunction "1_1") (pintype "passive"))
      (node (ref "C15") (pin "2") (pinfunction "2_2") (pintype "passive"))
      (node (ref "C16") (pin "2") (pinfunction "2_2") (pintype "passive"))
      (node (ref "C17") (pin "2") (pinfunction "2_2") (pintype "passive"))
      (node (ref "C18") (pin "2") (pinfunction "2_2") (pintype "passive"))
      (node (ref "C19") (pin "2") (pinfunction "2_2") (pintype "passive"))
      (node (ref "C2") (pin "2") (pinfunction "2_2") (pintype "passive"))
      (node (ref "C20") (pin "2") (pinfunction "2_2") (pintype "passive"))
      (node (ref "C21") (pin "2") (pinfunction "2_2") (pintype "passive"))
      (node (ref "C23") (pin "2") (pinfunction "2_2") (pintype "passive"))
      (node (ref "C25") (pin "2") (pinfunction "2_2") (pintype "passive"))
      (node (ref "C26") (pin "-") (pinfunction "-_-") (pintype "passive"))
      (node (ref "C27") (pin "-") (pinfunction "-_-") (pintype "passive"))
      (node (ref "C28") (pin "+") (pinfunction "+_+") (pintype "passive"))
      (node (ref "C29") (pin "-") (pinfunction "-_-") (pintype "passive"))
      (node (ref "C3") (pin "2") (pinfunction "2_2") (pintype "passive"))
      (node (ref "C30") (pin "2") (pinfunction "2_2") (pintype "passive"))
      (node (ref "C31") (pin "+") (pinfunction "+_+") (pintype "passive"))
      (node (ref "C4") (pin "2") (pinfunction "2_2") (pintype "passive"))
      (node (ref "C5") (pin "1") (pinfunction "1_1") (pintype "passive"))
      (node (ref "C9") (pin "-") (pinfunction "-_-") (pintype "passive"))
      (node (ref "D4") (pin "C") (pinfunction "C_C") (pintype "passive"))
      (node (ref "D6") (pin "A") (pinfunction "A_A") (pintype "passive"))
      (node (ref "D8") (pin "A") (pinfunction "A_A") (pintype "passive"))
      (node (ref "IC1") (pin "2") (pinfunction "C_2") (pintype "passive"))
      (node (ref "IC10") (pin "GND") (pinfunction "GND_GND") (pintype "input"))
      (node (ref "IC2") (pin "10") (pinfunction "+IN_10") (pintype "input"))
      (node (ref "IC2") (pin "12") (pinfunction "+IN_12") (pintype "input"))
      (node (ref "IC2") (pin "3") (pinfunction "+IN_3") (pintype "input"))
      (node (ref "IC2") (pin "5") (pinfunction "+IN_5") (pintype "input"))
      (node (ref "IC3") (pin "5") (pinfunction "LDAC_5") (pintype "input"))
      (node (ref "IC3") (pin "7") (pinfunction "AVSS_7") (pintype "power_in"))
      (node (ref "IC4") (pin "11") (pinfunction "GND_11") (pintype "power_in"))
      (node (ref "IC4") (pin "31") (pinfunction "GND_31") (pintype "power_in"))
      (node (ref "IC5") (pin "13") (pinfunction "G_13") (pintype "input"))
      (node (ref "IC5") (pin "8") (pinfunction "GND_8") (pintype "power_in"))
      (node (ref "IC6") (pin "10") (pinfunction "SER_10") (pintype "input"))
      (node (ref "IC6") (pin "15") (pinfunction "INH_15") (pintype "input"))
      (node (ref "IC6") (pin "5") (pinfunction "G_5") (pintype "input"))
      (node (ref "IC6") (pin "6") (pinfunction "H_6") (pintype "input"))
      (node (ref "IC6") (pin "8") (pinfunction "GND_8") (pintype "power_in"))
      (node (ref "IC7") (pin "3") (pinfunction "+IN_3") (pintype "input"))
      (node (ref "IC7") (pin "4") (pinfunction "V-_4") (pintype "power_in"))
      (node (ref "IC8") (pin "GND") (pinfunction "GND_GND") (pintype "input"))
      (node (ref "IC9") (pin "GND") (pinfunction "GND_GND") (pintype "input"))
      (node (ref "J1") (pin "GND") (pinfunction "1_GND") (pintype "passive"))
      (node (ref "J1") (pin "GND2") (pinfunction "4_GND2") (pintype "passive"))
      (node (ref "J2") (pin "GND") (pinfunction "1_GND") (pintype "passive"))
      (node (ref "J2") (pin "GND2") (pinfunction "4_GND2") (pintype "passive"))
      (node (ref "J3") (pin "GND") (pinfunction "1_GND") (pintype "passive"))
      (node (ref "J3") (pin "GND2") (pinfunction "4_GND2") (pintype "passive"))
      (node (ref "J4") (pin "GND") (pinfunction "1_GND") (pintype "passive"))
      (node (ref "J4") (pin "GND2") (pinfunction "4_GND2") (pintype "passive"))
      (node (ref "J5") (pin "GND") (pinfunction "1_GND") (pintype "passive"))
      (node (ref "J5") (pin "GND2") (pinfunction "4_GND2") (pintype "passive"))
      (node (ref "J6") (pin "GND") (pinfunction "1_GND") (pintype "passive"))
      (node (ref "J6") (pin "GND2") (pinfunction "4_GND2") (pintype "passive"))
      (node (ref "J6") (pin "SW") (pinfunction "3_SW") (pintype "passive"))
      (node (ref "J7") (pin "10") (pinfunction "10_10") (pintype "passive"))
      (node (ref "J7") (pin "11") (pinfunction "11_11") (pintype "passive"))
      (node (ref "J7") (pin "12") (pinfunction "12_12") (pintype "passive"))
      (node (ref "J7") (pin "13") (pinfunction "13_13") (pintype "passive"))
      (node (ref "J7") (pin "14") (pinfunction "14_14") (pintype "passive"))
      (node (ref "J7") (pin "9") (pinfunction "9_9") (pintype "passive"))
      (node (ref "J8") (pin "S") (pinfunction "S_S") (pintype "passive"))
      (node (ref "J8") (pin "SN") (pinfunction "SN_SN") (pintype "passive"))
      (node (ref "J9") (pin "1") (pinfunction "1_1") (pintype "passive"))
      (node (ref "LED1") (pin "K") (pinfunction "C_K") (pintype "passive"))
      (node (ref "LED2") (pin "K") (pinfunction "C_K") (pintype "passive"))
      (node (ref "LED3") (pin "K") (pinfunction "C_K") (pintype "passive"))
      (node (ref "LED4") (pin "K") (pinfunction "C_K") (pintype "passive"))
      (node (ref "LED5") (pin "K") (pinfunction "C_K") (pintype "passive"))
      (node (ref "LED6") (pin "K") (pinfunction "C_K") (pintype "passive"))
      (node (ref "OK1") (pin "5") (pinfunction "GND_5") (pintype "passive"))
      (node (ref "Q1") (pin "3") (pinfunction "E_3") (pintype "passive"))
      (node (ref "R31") (pin "1") (pinfunction "1_1") (pintype "passive"))
      (node (ref "R8") (pin "3") (pinfunction "A_3") (pintype "passive"))
      (node (ref "S1") (pin "1") (pinfunction "S_1") (pintype "passive"))
      (node (ref "S1") (pin "2") (pinfunction "S1_2") (pintype "passive"))
      (node (ref "S2") (pin "1") (pinfunction "S_1") (pintype "passive"))
      (node (ref "S2") (pin "2") (pinfunction "S1_2") (pintype "passive"))
      (node (ref "S3") (pin "1") (pinfunction "S_1") (pintype "passive"))
      (node (ref "S3") (pin "2") (pinfunction "S1_2") (pintype "passive"))
      (node (ref "S4") (pin "1") (pinfunction "S_1") (pintype "passive"))
      (node (ref "S4") (pin "2") (pinfunction "S1_2") (pintype "passive"))
      (node (ref "S5") (pin "1") (pinfunction "S_1") (pintype "passive"))
      (node (ref "S5") (pin "2") (pinfunction "S1_2") (pintype "passive"))
      (node (ref "S6") (pin "1") (pinfunction "S_1") (pintype "passive"))
      (node (ref "S6") (pin "2") (pinfunction "S1_2") (pintype "passive"))
      (node (ref "SW1") (pin "C") (pinfunction "C_C") (pintype "passive"))
      (node (ref "SW1") (pin "D") (pinfunction "1_D") (pintype "passive"))
      (node (ref "U$3") (pin "1") (pinfunction "VSS_1") (pintype "power_in"))
      (node (ref "U$3") (pin "16") (pinfunction "K_16") (pintype "power_in"))
      (node (ref "U$3") (pin "5") (pinfunction "R/W_5") (pintype "input"))
      (node (ref "U1") (pin "6") (pinfunction "6_6") (pintype "passive"))
    )
    (net (code "14") (name "IO_ENABLE") (class "Default")
      (node (ref "IC4") (pin "26") (pinfunction "(TDO)PC4_26") (pintype "bidirectional"))
      (node (ref "IC5") (pin "12") (pinfunction "RCK_12") (pintype "input"))
      (node (ref "IC6") (pin "1") (pinfunction "SH/~{LD}_1") (pintype "input"))
    )
    (net (code "15") (name "IO_INPUT") (class "Default")
      (node (ref "IC4") (pin "28") (pinfunction "(TOSC1)PC6_28") (pintype "bidirectional"))
      (node (ref "IC6") (pin "9") (pinfunction "QH_9") (pintype "output"))
    )
    (net (code "16") (name "IO_OUTPUT") (class "Default")
      (node (ref "IC4") (pin "27") (pinfunction "(TDI)PC5_27") (pintype "bidirectional"))
      (node (ref "IC5") (pin "14") (pinfunction "SER_14") (pintype "input"))
    )
    (net (code "17") (name "IO_SCK") (class "Default")
      (node (ref "IC4") (pin "29") (pinfunction "(TOSC2)PC7_29") (pintype "bidirectional"))
      (node (ref "IC5") (pin "11") (pinfunction "SCK_11") (pintype "input"))
      (node (ref "IC6") (pin "2") (pinfunction "CLK_2") (pintype "input"))
    )
    (net (code "18") (name "LCD_DATA4") (class "Default")
      (node (ref "IC4") (pin "36") (pinfunction "(ADC4)PA4_36") (pintype "bidirectional"))
      (node (ref "U$3") (pin "11") (pinfunction "DB4_11") (pintype "bidirectional"))
    )
    (net (code "19") (name "LCD_DATA5") (class "Default")
      (node (ref "IC4") (pin "35") (pinfunction "(ADC5)PA5_35") (pintype "bidirectional"))
      (node (ref "U$3") (pin "12") (pinfunction "DB5_12") (pintype "bidirectional"))
    )
    (net (code "20") (name "LCD_DATA6") (class "Default")
      (node (ref "IC4") (pin "34") (pinfunction "(ADC6)PA6_34") (pintype "bidirectional"))
      (node (ref "U$3") (pin "13") (pinfunction "DB6_13") (pintype "bidirectional"))
    )
    (net (code "21") (name "LCD_DATA7") (class "Default")
      (node (ref "IC4") (pin "33") (pinfunction "(ADC7)PA7_33") (pintype "bidirectional"))
      (node (ref "U$3") (pin "14") (pinfunction "DB7_14") (pintype "bidirectional"))
    )
    (net (code "22") (name "LCD_ENABLE") (class "Default")
      (node (ref "IC4") (pin "38") (pinfunction "(ADC2)PA2_38") (pintype "bidirectional"))
      (node (ref "U$3") (pin "6") (pinfunction "E_6") (pintype "input"))
    )
    (net (code "23") (name "LCD_RS") (class "Default")
      (node (ref "IC4") (pin "37") (pinfunction "(ADC3)PA3_37") (pintype "bidirectional"))
      (node (ref "U$3") (pin "4") (pinfunction "RS_4") (pintype "input"))
    )
    (net (code "24") (name "MIDI_IN") (class "Default")
      (node (ref "IC4") (pin "14") (pinfunction "(RXD)PD0_14") (pintype "bidirectional"))
      (node (ref "OK1") (pin "6") (pinfunction "VO_6") (pintype "passive"))
      (node (ref "R5") (pin "1") (pinfunction "1_1") (pintype "passive"))
    )
    (net (code "25") (name "MISO") (class "Default")
      (node (ref "IC4") (pin "7") (pinfunction "(MISO)PB6_7") (pintype "bidirectional"))
      (node (ref "U1") (pin "1") (pinfunction "1_1") (pintype "passive"))
    )
    (net (code "26") (name "MOSI") (class "Default")
      (node (ref "IC3") (pin "4") (pinfunction "SDI_4") (pintype "input"))
      (node (ref "IC4") (pin "6") (pinfunction "(MOSI)PB5_6") (pintype "bidirectional"))
      (node (ref "U1") (pin "4") (pinfunction "4_4") (pintype "passive"))
    )
    (net (code "27") (name "Net-(C1-Pad2)") (class "Default")
      (node (ref "C1") (pin "2") (pinfunction "2_2") (pintype "passive"))
      (node (ref "J8") (pin "T") (pinfunction "T_T") (pintype "passive"))
      (node (ref "R1") (pin "2") (pinfunction "2_2") (pintype "passive"))
      (node (ref "R4") (pin "2") (pinfunction "2_2") (pintype "passive"))
    )
    (net (code "28") (name "Net-(C6-Pad-)") (class "Default")
      (node (ref "C6") (pin "-") (pinfunction "-_-") (pintype "passive"))
      (node (ref "R11") (pin "1") (pinfunction "1_1") (pintype "passive"))
    )
    (net (code "29") (name "Net-(C10-Pad2)") (class "Default")
      (node (ref "C10") (pin "2") (pinfunction "2_2") (pintype "passive"))
      (node (ref "C31") (pin "-") (pinfunction "-_-") (pintype "passive"))
      (node (ref "D3") (pin "A") (pinfunction "A_A") (pintype "passive"))
      (node (ref "D5") (pin "A") (pinfunction "A_A") (pintype "passive"))
      (node (ref "IC10") (pin "IN") (pinfunction "IN_IN") (pintype "input"))
    )
    (net (code "30") (name "Net-(C12-Pad1)") (class "Default")
      (node (ref "C12") (pin "1") (pinfunction "1_1") (pintype "passive"))
      (node (ref "C19") (pin "1") (pinfunction "1_1") (pintype "passive"))
      (node (ref "C29") (pin "+") (pinfunction "+_+") (pintype "passive"))
      (node (ref "D2") (pin "C") (pinfunction "C_C") (pintype "passive"))
      (node (ref "D7") (pin "C") (pinfunction "C_C") (pintype "passive"))
      (node (ref "D9") (pin "C") (pinfunction "C_C") (pintype "passive"))
      (node (ref "IC8") (pin "IN") (pinfunction "IN_IN") (pintype "input"))
      (node (ref "IC9") (pin "IN") (pinfunction "IN_IN") (pintype "input"))
    )
    (net (code "31") (name "Net-(C24-Pad-)") (class "Default")
      (node (ref "C24") (pin "-") (pinfunction "-_-") (pintype "passive"))
      (node (ref "R29") (pin "1") (pinfunction "1_1") (pintype "passive"))
    )
    (net (code "32") (name "Net-(C30-Pad1)") (class "Default")
      (node (ref "C30") (pin "1") (pinfunction "1_1") (pintype "passive"))
      (node (ref "D2") (pin "A") (pinfunction "A_A") (pintype "passive"))
      (node (ref "D3") (pin "C") (pinfunction "C_C") (pintype "passive"))
      (node (ref "J9") (pin "3") (pinfunction "3_3") (pintype "passive"))
    )
    (net (code "33") (name "Net-(IC2A--IN)") (class "Default")
      (node (ref "C1") (pin "1") (pinfunction "1_1") (pintype "passive"))
      (node (ref "IC2") (pin "2") (pinfunction "-IN_2") (pintype "input"))
      (node (ref "R4") (pin "1") (pinfunction "1_1") (pintype "passive"))
      (node (ref "R7") (pin "2") (pinfunction "2_2") (pintype "passive"))
    )
    (net (code "34") (name "Net-(IC2A-OUT)") (class "Default")
      (node (ref "IC2") (pin "1") (pinfunction "OUT_1") (pintype "output"))
      (node (ref "R1") (pin "1") (pinfunction "1_1") (pintype "passive"))
    )
    (net (code "35") (name "Net-(IC2B--IN)") (class "Default")
      (node (ref "C7") (pin "1") (pinfunction "1_1") (pintype "passive"))
      (node (ref "IC2") (pin "6") (pinfunction "-IN_6") (pintype "input"))
      (node (ref "R11") (pin "2") (pinfunction "2_2") (pintype "passive"))
      (node (ref "R15") (pin "1") (pinfunction "1_1") (pintype "passive"))
    )
    (net (code "36") (name "Net-(IC2B-OUT)") (class "Default")
      (node (ref "C7") (pin "2") (pinfunction "2_2") (pintype "passive"))
      (node (ref "IC2") (pin "7") (pinfunction "OUT_7") (pintype "output"))
      (node (ref "J4") (pin "TIP") (pinfunction "2_TIP") (pintype "passive"))
      (node (ref "R15") (pin "2") (pinfunction "2_2") (pintype "passive"))
    )
    (net (code "37") (name "Net-(IC2C--IN)") (class "Default")
      (node (ref "C8") (pin "1") (pinfunction "1_1") (pintype "passive"))
      (node (ref "IC2") (pin "9") (pinfunction "-IN_9") (pintype "input"))
      (node (ref "R10") (pin "2") (pinfunction "2_2") (pintype "passive"))
      (node (ref "R12") (pin "2") (pinfunction "2_2") (pintype "passive"))
      (node (ref "R16") (pin "1") (pinfunction "1_1") (pintype "passive"))
    )
    (net (code "38") (name "Net-(IC2C-OUT)") (class "Default")
      (node (ref "C8") (pin "2") (pinfunction "2_2") (pintype "passive"))
      (node (ref "IC2") (pin "8") (pinfunction "OUT_8") (pintype "output"))
      (node (ref "J3") (pin "TIP") (pinfunction "2_TIP") (pintype "passive"))
      (node (ref "R16") (pin "2") (pinfunction "2_2") (pintype "passive"))
    )
    (net (code "39") (name "Net-(IC2D--IN)") (class "Default")
      (node (ref "IC2") (pin "13") (pinfunction "-IN_13") (pintype "input"))
      (node (ref "IC2") (pin "14") (pinfunction "OUT_14") (pintype "output"))
    )
    (net (code "40") (name "Net-(IC4-AREF)") (class "Default")
      (node (ref "C18") (pin "1") (pinfunction "1_1") (pintype "passive"))
      (node (ref "IC4") (pin "32") (pinfunction "AREF_32") (pintype "passive"))
    )
    (net (code "41") (name "Net-(IC4-XTAL1)") (class "Default")
      (node (ref "C13") (pin "2") (pinfunction "2_2") (pintype "passive"))
      (node (ref "IC4") (pin "13") (pinfunction "XTAL1_13") (pintype "bidirectional"))
      (node (ref "Q2") (pin "1") (pinfunction "1_1") (pintype "passive"))
    )
    (net (code "42") (name "Net-(IC4-XTAL2)") (class "Default")
      (node (ref "C14") (pin "2") (pinfunction "2_2") (pintype "passive"))
      (node (ref "IC4") (pin "12") (pinfunction "XTAL2_12") (pintype "bidirectional"))
      (node (ref "Q2") (pin "2") (pinfunction "2_2") (pintype "passive"))
    )
    (net (code "43") (name "Net-(IC5A-QA)") (class "Default")
      (node (ref "IC5") (pin "15") (pinfunction "QA_15") (pintype "tri_state"))
      (node (ref "R19") (pin "1") (pinfunction "1_1") (pintype "passive"))
    )
    (net (code "44") (name "Net-(IC5A-QB)") (class "Default")
      (node (ref "IC5") (pin "1") (pinfunction "QB_1") (pintype "tri_state"))
      (node (ref "R20") (pin "1") (pinfunction "1_1") (pintype "passive"))
    )
    (net (code "45") (name "Net-(IC5A-QC)") (class "Default")
      (node (ref "IC5") (pin "2") (pinfunction "QC_2") (pintype "tri_state"))
      (node (ref "R21") (pin "1") (pinfunction "1_1") (pintype "passive"))
    )
    (net (code "46") (name "Net-(IC5A-QD)") (class "Default")
      (node (ref "IC5") (pin "3") (pinfunction "QD_3") (pintype "tri_state"))
      (node (ref "R22") (pin "1") (pinfunction "1_1") (pintype "passive"))
    )
    (net (code "47") (name "Net-(IC5A-QE)") (class "Default")
      (node (ref "IC5") (pin "4") (pinfunction "QE_4") (pintype "tri_state"))
      (node (ref "R23") (pin "1") (pinfunction "1_1") (pintype "passive"))
    )
    (net (code "48") (name "Net-(IC5A-QF)") (class "Default")
      (node (ref "IC5") (pin "5") (pinfunction "QF_5") (pintype "tri_state"))
      (node (ref "R24") (pin "1") (pinfunction "1_1") (pintype "passive"))
    )
    (net (code "49") (name "Net-(IC6A-A)") (class "Default")
      (node (ref "IC6") (pin "11") (pinfunction "A_11") (pintype "input"))
      (node (ref "RN1") (pin "7") (pinfunction "7_7") (pintype "passive"))
      (node (ref "S1") (pin "3") (pinfunction "P_3") (pintype "passive"))
      (node (ref "S1") (pin "4") (pinfunction "P1_4") (pintype "passive"))
    )
    (net (code "50") (name "Net-(IC6A-B)") (class "Default")
      (node (ref "IC6") (pin "12") (pinfunction "B_12") (pintype "input"))
      (node (ref "RN1") (pin "6") (pinfunction "6_6") (pintype "passive"))
      (node (ref "S2") (pin "3") (pinfunction "P_3") (pintype "passive"))
      (node (ref "S2") (pin "4") (pinfunction "P1_4") (pintype "passive"))
    )
    (net (code "51") (name "Net-(IC6A-C)") (class "Default")
      (node (ref "IC6") (pin "13") (pinfunction "C_13") (pintype "input"))
      (node (ref "RN1") (pin "5") (pinfunction "5_5") (pintype "passive"))
      (node (ref "S3") (pin "3") (pinfunction "P_3") (pintype "passive"))
      (node (ref "S3") (pin "4") (pinfunction "P1_4") (pintype "passive"))
    )
    (net (code "52") (name "Net-(IC6A-D)") (class "Default")
      (node (ref "IC6") (pin "14") (pinfunction "D_14") (pintype "input"))
      (node (ref "RN1") (pin "4") (pinfunction "4_4") (pintype "passive"))
      (node (ref "S4") (pin "3") (pinfunction "P_3") (pintype "passive"))
      (node (ref "S4") (pin "4") (pinfunction "P1_4") (pintype "passive"))
    )
    (net (code "53") (name "Net-(IC6A-E)") (class "Default")
      (node (ref "IC6") (pin "3") (pinfunction "E_3") (pintype "input"))
      (node (ref "RN1") (pin "3") (pinfunction "3_3") (pintype "passive"))
      (node (ref "S5") (pin "3") (pinfunction "P_3") (pintype "passive"))
      (node (ref "S5") (pin "4") (pinfunction "P1_4") (pintype "passive"))
    )
    (net (code "54") (name "Net-(IC6A-F)") (class "Default")
      (node (ref "IC6") (pin "4") (pinfunction "F_4") (pintype "input"))
      (node (ref "RN1") (pin "2") (pinfunction "2_2") (pintype "passive"))
      (node (ref "S6") (pin "3") (pinfunction "P_3") (pintype "passive"))
      (node (ref "S6") (pin "4") (pinfunction "P1_4") (pintype "passive"))
    )
    (net (code "55") (name "Net-(IC7A--IN)") (class "Default")
      (node (ref "IC7") (pin "2") (pinfunction "-IN_2") (pintype "input"))
      (node (ref "R30") (pin "1") (pinfunction "1_1") (pintype "passive"))
      (node (ref "R32") (pin "2") (pinfunction "2_2") (pintype "passive"))
    )
    (net (code "56") (name "Net-(IC7B-+IN)") (class "Default")
      (node (ref "C25") (pin "1") (pinfunction "1_1") (pintype "passive"))
      (node (ref "IC7") (pin "5") (pinfunction "+IN_5") (pintype "input"))
      (node (ref "R31") (pin "2") (pinfunction "2_2") (pintype "passive"))
      (node (ref "R33") (pin "1") (pinfunction "1_1") (pintype "passive"))
    )
    (net (code "57") (name "Net-(IC7B--IN)") (class "Default")
      (node (ref "C22") (pin "1") (pinfunction "1_1") (pintype "passive"))
      (node (ref "IC7") (pin "6") (pinfunction "-IN_6") (pintype "input"))
      (node (ref "R28") (pin "1") (pinfunction "1_1") (pintype "passive"))
      (node (ref "R29") (pin "2") (pinfunction "2_2") (pintype "passive"))
    )
    (net (code "58") (name "Net-(J1-2)") (class "Default")
      (node (ref "J1") (pin "TIP") (pinfunction "2_TIP") (pintype "passive"))
      (node (ref "R25") (pin "2") (pinfunction "2_2") (pintype "passive"))
    )
    (net (code "59") (name "Net-(J2-2)") (class "Default")
      (node (ref "J2") (pin "TIP") (pinfunction "2_TIP") (pintype "passive"))
      (node (ref "R27") (pin "2") (pinfunction "2_2") (pintype "passive"))
    )
    (net (code "60") (name "Net-(J5-2)") (class "Default")
      (node (ref "C24") (pin "+") (pinfunction "+_+") (pintype "passive"))
      (node (ref "J5") (pin "TIP") (pinfunction "2_TIP") (pintype "passive"))
      (node (ref "R32") (pin "1") (pinfunction "1_1") (pintype "passive"))
      (node (ref "R7") (pin "1") (pinfunction "1_1") (pintype "passive"))
    )
    (net (code "61") (name "Net-(J6-2)") (class "Default")
      (node (ref "J6") (pin "TIP") (pinfunction "2_TIP") (pintype "passive"))
      (node (ref "R18") (pin "1") (pinfunction "1_1") (pintype "passive"))
    )
    (net (code "62") (name "Net-(LED1-PadA)") (class "Default")
      (node (ref "LED1") (pin "A") (pinfunction "A_A") (pintype "passive"))
      (node (ref "R19") (pin "2") (pinfunction "2_2") (pintype "passive"))
    )
    (net (code "63") (name "Net-(LED2-PadA)") (class "Default")
      (node (ref "LED2") (pin "A") (pinfunction "A_A") (pintype "passive"))
      (node (ref "R20") (pin "2") (pinfunction "2_2") (pintype "passive"))
    )
    (net (code "64") (name "Net-(LED3-PadA)") (class "Default")
      (node (ref "LED3") (pin "A") (pinfunction "A_A") (pintype "passive"))
      (node (ref "R21") (pin "2") (pinfunction "2_2") (pintype "passive"))
    )
    (net (code "65") (name "Net-(LED4-PadA)") (class "Default")
      (node (ref "LED4") (pin "A") (pinfunction "A_A") (pintype "passive"))
      (node (ref "R22") (pin "2") (pinfunction "2_2") (pintype "passive"))
    )
    (net (code "66") (name "Net-(LED5-PadA)") (class "Default")
      (node (ref "LED5") (pin "A") (pinfunction "A_A") (pintype "passive"))
      (node (ref "R23") (pin "2") (pinfunction "2_2") (pintype "passive"))
    )
    (net (code "67") (name "Net-(LED6-PadA)") (class "Default")
      (node (ref "LED6") (pin "A") (pinfunction "A_A") (pintype "passive"))
      (node (ref "R24") (pin "2") (pinfunction "2_2") (pintype "passive"))
    )
    (net (code "68") (name "Net-(OK1-A)") (class "Default")
      (node (ref "D1") (pin "C") (pinfunction "C_C") (pintype "passive"))
      (node (ref "OK1") (pin "2") (pinfunction "A_2") (pintype "passive"))
      (node (ref "R3") (pin "2") (pinfunction "2_2") (pintype "passive"))
    )
    (net (code "69") (name "Net-(OK1-C)") (class "Default")
      (node (ref "D1") (pin "A") (pinfunction "A_A") (pintype "passive"))
      (node (ref "OK1") (pin "3") (pinfunction "C_3") (pintype "passive"))
      (node (ref "X1") (pin "5") (pinfunction "5_5") (pintype "passive"))
    )
    (net (code "70") (name "Net-(Q1-B)") (class "Default")
      (node (ref "Q1") (pin "2") (pinfunction "B_2") (pintype "passive"))
      (node (ref "R18") (pin "2") (pinfunction "2_2") (pintype "passive"))
    )
    (net (code "71") (name "Net-(R3-Pad1)") (class "Default")
      (node (ref "R3") (pin "1") (pinfunction "1_1") (pintype "passive"))
      (node (ref "X1") (pin "4") (pinfunction "4_4") (pintype "passive"))
    )
    (net (code "72") (name "Net-(R8-S)") (class "Default")
      (node (ref "R8") (pin "2") (pinfunction "S_2") (pintype "passive"))
      (node (ref "U$3") (pin "3") (pinfunction "VO_3") (pintype "bidirectional"))
    )
    (net (code "73") (name "Net-(R9-E)") (class "Default")
      (node (ref "R6") (pin "1") (pinfunction "1_1") (pintype "passive"))
      (node (ref "R9") (pin "1") (pinfunction "E_1") (pintype "passive"))
    )
    (net (code "74") (name "Net-(R10-Pad1)") (class "Default")
      (node (ref "R10") (pin "1") (pinfunction "1_1") (pintype "passive"))
      (node (ref "R6") (pin "2") (pinfunction "2_2") (pintype "passive"))
    )
    (net (code "75") (name "Net-(R13-E)") (class "Default")
      (node (ref "R12") (pin "1") (pinfunction "1_1") (pintype "passive"))
      (node (ref "R13") (pin "1") (pinfunction "E_1") (pintype "passive"))
    )
    (net (code "76") (name "Net-(U$3-A)") (class "Default")
      (node (ref "R14") (pin "2") (pinfunction "2_2") (pintype "passive"))
      (node (ref "U$3") (pin "15") (pinfunction "A_15") (pintype "power_in"))
    )
    (net (code "77") (name "PITCH_DETECTOR") (class "Default")
      (node (ref "IC4") (pin "20") (pinfunction "(ICP)PD6_20") (pintype "bidirectional"))
      (node (ref "IC7") (pin "1") (pinfunction "OUT_1") (pintype "output"))
      (node (ref "R30") (pin "2") (pinfunction "2_2") (pintype "passive"))
    )
    (net (code "78") (name "REF_-4.096") (class "Default")
      (node (ref "C3") (pin "1") (pinfunction "1_1") (pintype "passive"))
      (node (ref "IC1") (pin "3") (pinfunction "A_3") (pintype "passive"))
      (node (ref "R2") (pin "2") (pinfunction "2_2") (pintype "passive"))
      (node (ref "R9") (pin "2") (pinfunction "S_2") (pintype "passive"))
      (node (ref "R9") (pin "3") (pinfunction "A_3") (pintype "passive"))
    )
    (net (code "79") (name "RESET") (class "Default")
      (node (ref "C20") (pin "1") (pinfunction "1_1") (pintype "passive"))
      (node (ref "IC4") (pin "9") (pinfunction "RESET_9") (pintype "input"))
      (node (ref "R26") (pin "1") (pinfunction "1_1") (pintype "passive"))
      (node (ref "U1") (pin "5") (pinfunction "5_5") (pintype "passive"))
    )
    (net (code "80") (name "SCK") (class "Default")
      (node (ref "IC3") (pin "3") (pinfunction "SCK_3") (pintype "input"))
      (node (ref "IC4") (pin "8") (pinfunction "(SCK)PB7_8") (pintype "bidirectional"))
      (node (ref "U1") (pin "3") (pinfunction "3_3") (pintype "passive"))
    )
    (net (code "81") (name "SS") (class "Default")
      (node (ref "IC3") (pin "2") (pinfunction "#CS_2") (pintype "input"))
      (node (ref "IC4") (pin "5") (pinfunction "(SS)PB4_5") (pintype "bidirectional"))
    )
    (net (code "82") (name "VCC") (class "Default")
      (node (ref "C27") (pin "+") (pinfunction "+_+") (pintype "passive"))
      (node (ref "C4") (pin "1") (pinfunction "1_1") (pintype "passive"))
      (node (ref "D6") (pin "C") (pinfunction "C_C") (pintype "passive"))
      (node (ref "D7") (pin "A") (pinfunction "A_A") (pintype "passive"))
      (node (ref "IC2") (pin "4") (pinfunction "V+_4") (pintype "power_in"))
      (node (ref "IC9") (pin "OUT") (pinfunction "OUT_OUT") (pintype "passive"))
      (node (ref "J7") (pin "7") (pinfunction "7_7") (pintype "passive"))
      (node (ref "J7") (pin "8") (pinfunction "8_8") (pintype "passive"))
    )
    (net (code "83") (name "VEE") (class "Default")
      (node (ref "C28") (pin "-") (pinfunction "-_-") (pintype "passive"))
      (node (ref "C5") (pin "2") (pinfunction "2_2") (pintype "passive"))
      (node (ref "D4") (pin "A") (pinfunction "A_A") (pintype "passive"))
      (node (ref "D5") (pin "C") (pinfunction "C_C") (pintype "passive"))
      (node (ref "IC10") (pin "OUT") (pinfunction "OUT_OUT") (pintype "passive"))
      (node (ref "IC2") (pin "11") (pinfunction "V-_11") (pintype "power_in"))
      (node (ref "J7") (pin "15") (pinfunction "15_15") (pintype "passive"))
      (node (ref "J7") (pin "16") (pinfunction "16_16") (pintype "passive"))
      (node (ref "R2") (pin "1") (pinfunction "1_1") (pintype "passive"))
    )
    (net (code "84") (name "unconnected-(IC4-(ADC1)PA1-Pad39)") (class "Default")
      (node (ref "IC4") (pin "39") (pinfunction "(ADC1)PA1_39") (pintype "bidirectional"))
    )
    (net (code "85") (name "unconnected-(IC4-(AIN0{slash}INT2)PB2-Pad3)") (class "Default")
      (node (ref "IC4") (pin "3") (pinfunction "(AIN0/INT2)PB2_3") (pintype "bidirectional"))
    )
    (net (code "86") (name "unconnected-(IC4-(AIN1{slash}OC0)PB3-Pad4)") (class "Default")
      (node (ref "IC4") (pin "4") (pinfunction "(AIN1/OC0)PB3_4") (pintype "bidirectional"))
    )
    (net (code "87") (name "unconnected-(IC4-(OC1A)PD5-Pad19)") (class "Default")
      (node (ref "IC4") (pin "19") (pinfunction "(OC1A)PD5_19") (pintype "bidirectional"))
    )
    (net (code "88") (name "unconnected-(IC4-(OC2)PD7-Pad21)") (class "Default")
      (node (ref "IC4") (pin "21") (pinfunction "(OC2)PD7_21") (pintype "bidirectional"))
    )
    (net (code "89") (name "unconnected-(IC4-(T0{slash}XCK)PB0-Pad1)") (class "Default")
      (node (ref "IC4") (pin "1") (pinfunction "(T0/XCK)PB0_1") (pintype "bidirectional"))
    )
    (net (code "90") (name "unconnected-(IC4-(T1)PB1-Pad2)") (class "Default")
      (node (ref "IC4") (pin "2") (pinfunction "(T1)PB1_2") (pintype "bidirectional"))
    )
    (net (code "91") (name "unconnected-(IC4-(TMS)PC3-Pad25)") (class "Default")
      (node (ref "IC4") (pin "25") (pinfunction "(TMS)PC3_25") (pintype "bidirectional"))
    )
    (net (code "92") (name "unconnected-(IC4-(TXD)PD1-Pad15)") (class "Default")
      (node (ref "IC4") (pin "15") (pinfunction "(TXD)PD1_15") (pintype "bidirectional"))
    )
    (net (code "93") (name "unconnected-(IC5A-QG-Pad6)") (class "Default")
      (node (ref "IC5") (pin "6") (pinfunction "QG_6") (pintype "tri_state"))
    )
    (net (code "94") (name "unconnected-(IC5A-QH*-Pad9)") (class "Default")
      (node (ref "IC5") (pin "9") (pinfunction "QH*_9") (pintype "tri_state"))
    )
    (net (code "95") (name "unconnected-(IC5A-QH-Pad7)") (class "Default")
      (node (ref "IC5") (pin "7") (pinfunction "QH_7") (pintype "tri_state"))
    )
    (net (code "96") (name "unconnected-(IC6A-~{QH}-Pad7)") (class "Default")
      (node (ref "IC6") (pin "7") (pinfunction "~{QH}_7") (pintype "output"))
    )
    (net (code "97") (name "unconnected-(J1-3-PadSW)") (class "Default")
      (node (ref "J1") (pin "SW") (pinfunction "3_SW") (pintype "passive"))
    )
    (net (code "98") (name "unconnected-(J2-3-PadSW)") (class "Default")
      (node (ref "J2") (pin "SW") (pinfunction "3_SW") (pintype "passive"))
    )
    (net (code "99") (name "unconnected-(J3-3-PadSW)") (class "Default")
      (node (ref "J3") (pin "SW") (pinfunction "3_SW") (pintype "passive"))
    )
    (net (code "100") (name "unconnected-(J4-3-PadSW)") (class "Default")
      (node (ref "J4") (pin "SW") (pinfunction "3_SW") (pintype "passive"))
    )
    (net (code "101") (name "unconnected-(J5-3-PadSW)") (class "Default")
      (node (ref "J5") (pin "SW") (pinfunction "3_SW") (pintype "passive"))
    )
    (net (code "102") (name "unconnected-(J7-Pad1)") (class "Default")
      (node (ref "J7") (pin "1") (pinfunction "1_1") (pintype "passive"))
    )
    (net (code "103") (name "unconnected-(J7-Pad2)") (class "Default")
      (node (ref "J7") (pin "2") (pinfunction "2_2") (pintype "passive"))
    )
    (net (code "104") (name "unconnected-(J7-Pad3)") (class "Default")
      (node (ref "J7") (pin "3") (pinfunction "3_3") (pintype "passive"))
    )
    (net (code "105") (name "unconnected-(J7-Pad4)") (class "Default")
      (node (ref "J7") (pin "4") (pinfunction "4_4") (pintype "passive"))
    )
    (net (code "106") (name "unconnected-(J8-PadTN)") (class "Default")
      (node (ref "J8") (pin "TN") (pinfunction "TN_TN") (pintype "passive"))
    )
    (net (code "107") (name "unconnected-(J9-Pad2)") (class "Default")
      (node (ref "J9") (pin "2") (pinfunction "2_2") (pintype "passive"))
    )
    (net (code "108") (name "unconnected-(OK1-VB-Pad7)") (class "Default")
      (node (ref "OK1") (pin "7") (pinfunction "VB_7") (pintype "passive"))
    )
    (net (code "109") (name "unconnected-(U$3-DB0-Pad7)") (class "Default")
      (node (ref "U$3") (pin "7") (pinfunction "DB0_7") (pintype "bidirectional"))
    )
    (net (code "110") (name "unconnected-(U$3-DB1-Pad8)") (class "Default")
      (node (ref "U$3") (pin "8") (pinfunction "DB1_8") (pintype "bidirectional"))
    )
    (net (code "111") (name "unconnected-(U$3-DB2-Pad9)") (class "Default")
      (node (ref "U$3") (pin "9") (pinfunction "DB2_9") (pintype "bidirectional"))
    )
    (net (code "112") (name "unconnected-(U$3-DB3-Pad10)") (class "Default")
      (node (ref "U$3") (pin "10") (pinfunction "DB3_10") (pintype "bidirectional"))
    )
    (net (code "113") (name "unconnected-(X1-Pad1)") (class "Default")
      (node (ref "X1") (pin "1") (pinfunction "1_1") (pintype "passive"))
    )
    (net (code "114") (name "unconnected-(X1-Pad2)") (class "Default")
      (node (ref "X1") (pin "2") (pinfunction "2_2") (pintype "passive"))
    )
    (net (code "115") (name "unconnected-(X1-Pad3)") (class "Default")
      (node (ref "X1") (pin "3") (pinfunction "3_3") (pintype "passive"))
    )
  )
)
